# kapcsol.net
KiCad netlist of a schematic drawn in EAGLE
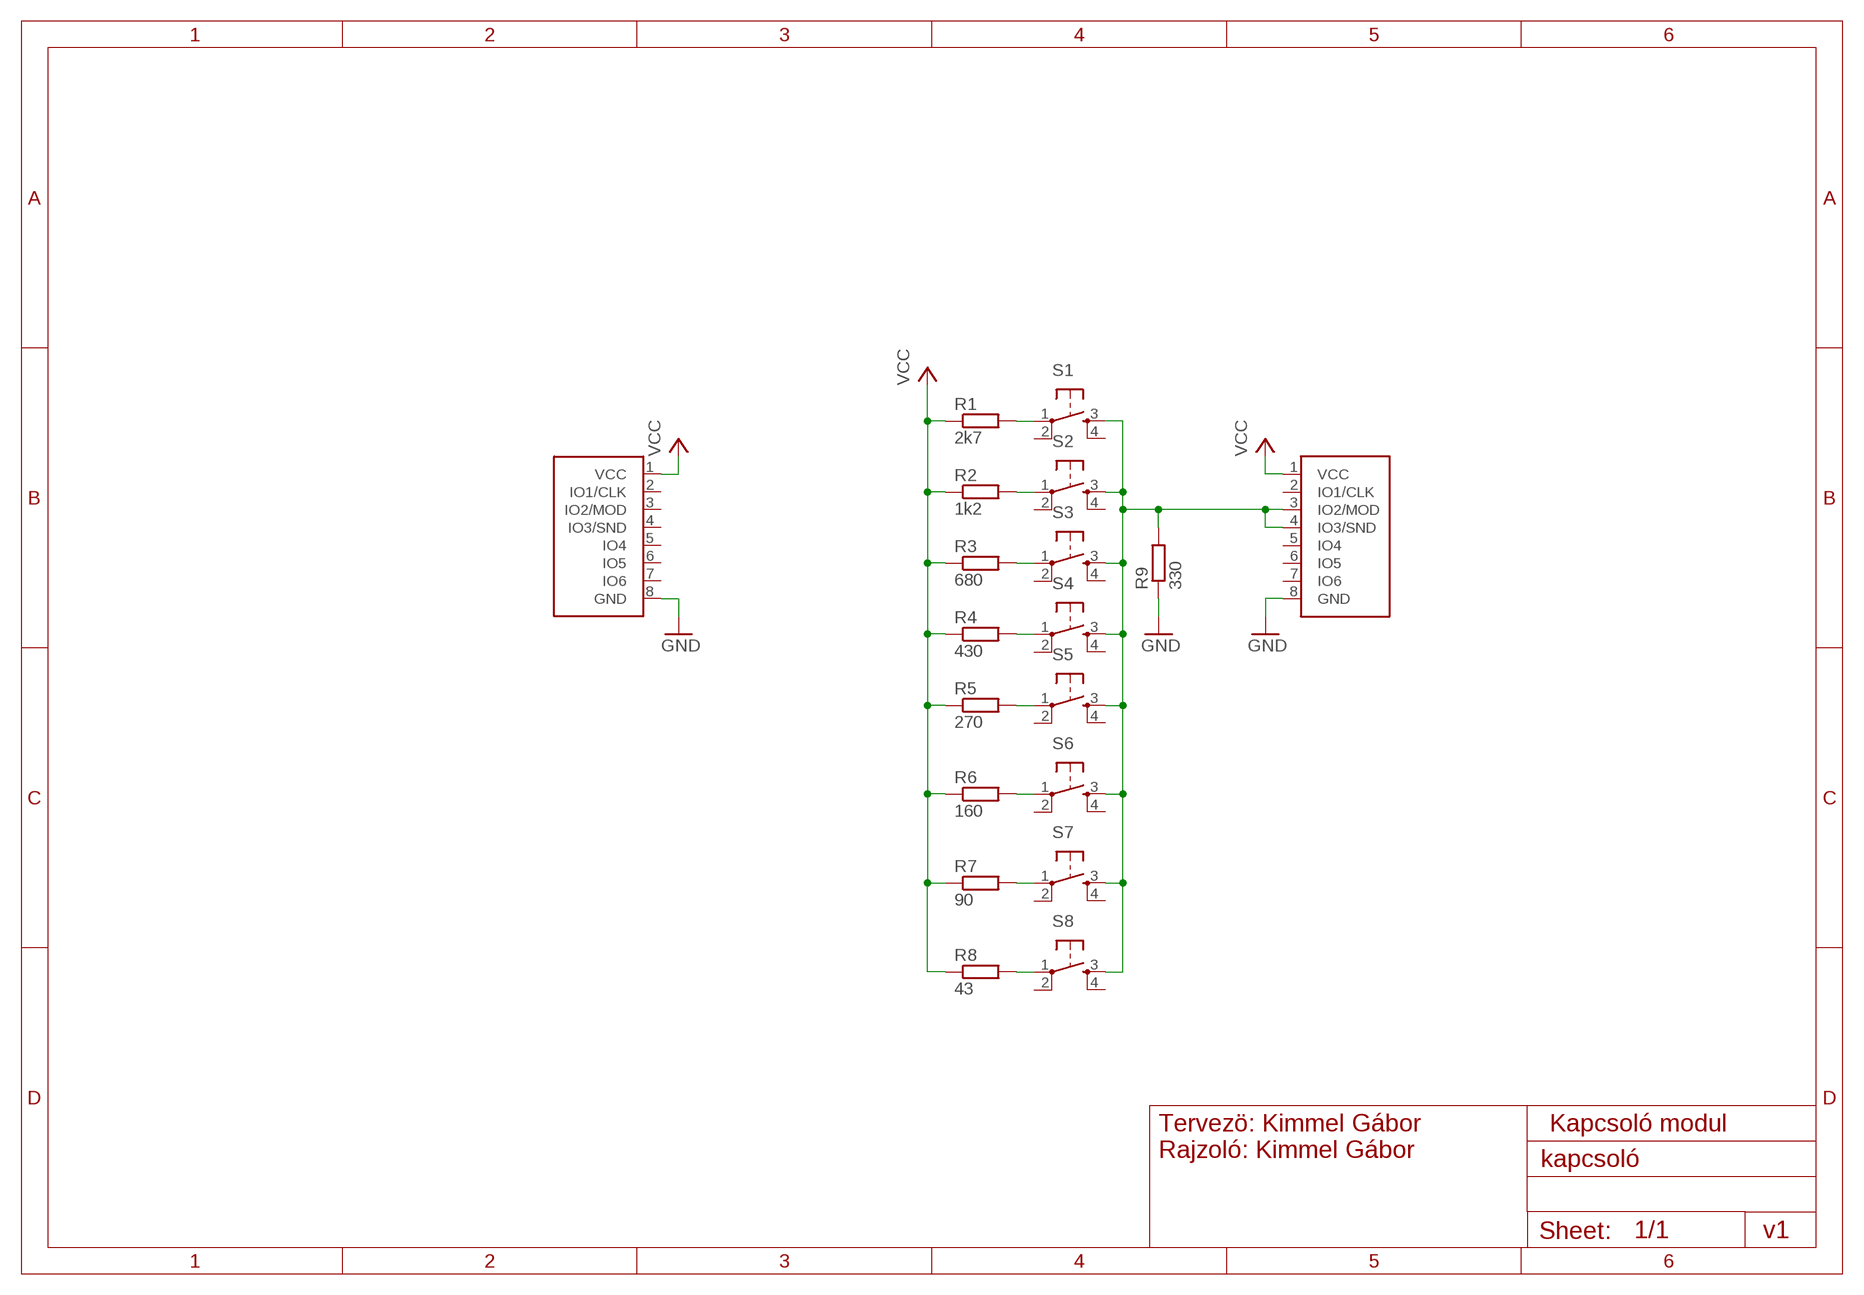
[diagram p0: schematic, sheet 1]

(export (version "E")
  (design (tool "Eeschema 10.0.6"))
  (components
    (comp (ref "R1")
      (value "2k7")
      (footprint "eagle-import:0309_12")
      (libsource (lib "eagle-import") (part "R-EU_0309/12"))
    )
    (comp (ref "R2")
      (value "1k2")
      (footprint "eagle-import:0309_12")
      (libsource (lib "eagle-import") (part "R-EU_0309/12"))
    )
    (comp (ref "R3")
      (value "680")
      (footprint "eagle-import:0309_12")
      (libsource (lib "eagle-import") (part "R-EU_0309/12"))
    )
    (comp (ref "R4")
      (value "430")
      (footprint "eagle-import:0309_12")
      (libsource (lib "eagle-import") (part "R-EU_0309/12"))
    )
    (comp (ref "R5")
      (value "270")
      (footprint "eagle-import:0309_12")
      (libsource (lib "eagle-import") (part "R-EU_0309/12"))
    )
    (comp (ref "R6")
      (value "160")
      (footprint "eagle-import:0309_12")
      (libsource (lib "eagle-import") (part "R-EU_0309/12"))
    )
    (comp (ref "R7")
      (value "90")
      (footprint "eagle-import:0309_12")
      (libsource (lib "eagle-import") (part "R-EU_0309/12"))
    )
    (comp (ref "R8")
      (value "43")
      (footprint "eagle-import:0309_12")
      (libsource (lib "eagle-import") (part "R-EU_0309/12"))
    )
    (comp (ref "R9")
      (value "330")
      (footprint "eagle-import:0309_12")
      (libsource (lib "eagle-import") (part "R-EU_0309/12"))
    )
    (comp (ref "S1")
      (value "TAC_SWITCHPTH")
      (footprint "eagle-import:TACTILE-PTH")
      (libsource (lib "eagle-import") (part "TAC_SWITCHPTH"))
    )
    (comp (ref "S2")
      (value "TAC_SWITCHPTH")
      (footprint "eagle-import:TACTILE-PTH")
      (libsource (lib "eagle-import") (part "TAC_SWITCHPTH"))
    )
    (comp (ref "S3")
      (value "TAC_SWITCHPTH")
      (footprint "eagle-import:TACTILE-PTH")
      (libsource (lib "eagle-import") (part "TAC_SWITCHPTH"))
    )
    (comp (ref "S4")
      (value "TAC_SWITCHPTH")
      (footprint "eagle-import:TACTILE-PTH")
      (libsource (lib "eagle-import") (part "TAC_SWITCHPTH"))
    )
    (comp (ref "S5")
      (value "TAC_SWITCHPTH")
      (footprint "eagle-import:TACTILE-PTH")
      (libsource (lib "eagle-import") (part "TAC_SWITCHPTH"))
    )
    (comp (ref "S6")
      (value "TAC_SWITCHPTH")
      (footprint "eagle-import:TACTILE-PTH")
      (libsource (lib "eagle-import") (part "TAC_SWITCHPTH"))
    )
    (comp (ref "S7")
      (value "TAC_SWITCHPTH")
      (footprint "eagle-import:TACTILE-PTH")
      (libsource (lib "eagle-import") (part "TAC_SWITCHPTH"))
    )
    (comp (ref "S8")
      (value "TAC_SWITCHPTH")
      (footprint "eagle-import:TACTILE-PTH")
      (libsource (lib "eagle-import") (part "TAC_SWITCHPTH"))
    )
    (comp (ref "U$1")
      (value "GANZ-CONNECTOR-OUT")
      (footprint "eagle-import:MA08-1W")
      (libsource (lib "eagle-import") (part "GANZ-CONNECTOR-OUT"))
    )
    (comp (ref "U$2")
      (value "GANZ-CONNECTOR")
      (footprint "eagle-import:FE08W")
      (libsource (lib "eagle-import") (part "GANZ-CONNECTOR"))
    )
  )
  (nets
    (net (code "1") (name "GND") (class "Default")
      (node (ref "R9") (pin "1") (pinfunction "1_1") (pintype "passive"))
      (node (ref "U$1") (pin "8") (pinfunction "GND_8") (pintype "bidirectional"))
      (node (ref "U$2") (pin "8") (pinfunction "GND_8") (pintype "bidirectional"))
    )
    (net (code "2") (name "Net-(R1-Pad2)") (class "Default")
      (node (ref "R1") (pin "2") (pinfunction "2_2") (pintype "passive"))
      (node (ref "S1") (pin "1") (pinfunction "1_1") (pintype "passive"))
    )
    (net (code "3") (name "Net-(R2-Pad2)") (class "Default")
      (node (ref "R2") (pin "2") (pinfunction "2_2") (pintype "passive"))
      (node (ref "S2") (pin "1") (pinfunction "1_1") (pintype "passive"))
    )
    (net (code "4") (name "Net-(R3-Pad2)") (class "Default")
      (node (ref "R3") (pin "2") (pinfunction "2_2") (pintype "passive"))
      (node (ref "S3") (pin "1") (pinfunction "1_1") (pintype "passive"))
    )
    (net (code "5") (name "Net-(R4-Pad2)") (class "Default")
      (node (ref "R4") (pin "2") (pinfunction "2_2") (pintype "passive"))
      (node (ref "S4") (pin "1") (pinfunction "1_1") (pintype "passive"))
    )
    (net (code "6") (name "Net-(R5-Pad2)") (class "Default")
      (node (ref "R5") (pin "2") (pinfunction "2_2") (pintype "passive"))
      (node (ref "S5") (pin "1") (pinfunction "1_1") (pintype "passive"))
    )
    (net (code "7") (name "Net-(R6-Pad2)") (class "Default")
      (node (ref "R6") (pin "2") (pinfunction "2_2") (pintype "passive"))
      (node (ref "S6") (pin "1") (pinfunction "1_1") (pintype "passive"))
    )
    (net (code "8") (name "Net-(R7-Pad2)") (class "Default")
      (node (ref "R7") (pin "2") (pinfunction "2_2") (pintype "passive"))
      (node (ref "S7") (pin "1") (pinfunction "1_1") (pintype "passive"))
    )
    (net (code "9") (name "Net-(R8-Pad2)") (class "Default")
      (node (ref "R8") (pin "2") (pinfunction "2_2") (pintype "passive"))
      (node (ref "S8") (pin "1") (pinfunction "1_1") (pintype "passive"))
    )
    (net (code "10") (name "Net-(U$1-IO2{slash}MOD)") (class "Default")
      (node (ref "R9") (pin "2") (pinfunction "2_2") (pintype "passive"))
      (node (ref "S1") (pin "3") (pinfunction "3_3") (pintype "passive"))
      (node (ref "S2") (pin "3") (pinfunction "3_3") (pintype "passive"))
      (node (ref "S3") (pin "3") (pinfunction "3_3") (pintype "passive"))
      (node (ref "S4") (pin "3") (pinfunction "3_3") (pintype "passive"))
      (node (ref "S5") (pin "3") (pinfunction "3_3") (pintype "passive"))
      (node (ref "S6") (pin "3") (pinfunction "3_3") (pintype "passive"))
      (node (ref "S7") (pin "3") (pinfunction "3_3") (pintype "passive"))
      (node (ref "S8") (pin "3") (pinfunction "3_3") (pintype "passive"))
      (node (ref "U$1") (pin "3") (pinfunction "IO2/MOD_3") (pintype "bidirectional"))
      (node (ref "U$1") (pin "4") (pinfunction "IO3/SND_4") (pintype "bidirectional"))
    )
    (net (code "11") (name "VCC") (class "Default")
      (node (ref "R1") (pin "1") (pinfunction "1_1") (pintype "passive"))
      (node (ref "R2") (pin "1") (pinfunction "1_1") (pintype "passive"))
      (node (ref "R3") (pin "1") (pinfunction "1_1") (pintype "passive"))
      (node (ref "R4") (pin "1") (pinfunction "1_1") (pintype "passive"))
      (node (ref "R5") (pin "1") (pinfunction "1_1") (pintype "passive"))
      (node (ref "R6") (pin "1") (pinfunction "1_1") (pintype "passive"))
      (node (ref "R7") (pin "1") (pinfunction "1_1") (pintype "passive"))
      (node (ref "R8") (pin "1") (pinfunction "1_1") (pintype "passive"))
      (node (ref "U$1") (pin "1") (pinfunction "VCC_1") (pintype "bidirectional"))
      (node (ref "U$2") (pin "1") (pinfunction "VCC_1") (pintype "bidirectional"))
    )
    (net (code "12") (name "unconnected-(S1-Pad2)") (class "Default")
      (node (ref "S1") (pin "2") (pinfunction "2_2") (pintype "passive"))
    )
    (net (code "13") (name "unconnected-(S1-Pad4)") (class "Default")
      (node (ref "S1") (pin "4") (pinfunction "4_4") (pintype "passive"))
    )
    (net (code "14") (name "unconnected-(S2-Pad2)") (class "Default")
      (node (ref "S2") (pin "2") (pinfunction "2_2") (pintype "passive"))
    )
    (net (code "15") (name "unconnected-(S2-Pad4)") (class "Default")
      (node (ref "S2") (pin "4") (pinfunction "4_4") (pintype "passive"))
    )
    (net (code "16") (name "unconnected-(S3-Pad2)") (class "Default")
      (node (ref "S3") (pin "2") (pinfunction "2_2") (pintype "passive"))
    )
    (net (code "17") (name "unconnected-(S3-Pad4)") (class "Default")
      (node (ref "S3") (pin "4") (pinfunction "4_4") (pintype "passive"))
    )
    (net (code "18") (name "unconnected-(S4-Pad2)") (class "Default")
      (node (ref "S4") (pin "2") (pinfunction "2_2") (pintype "passive"))
    )
    (net (code "19") (name "unconnected-(S4-Pad4)") (class "Default")
      (node (ref "S4") (pin "4") (pinfunction "4_4") (pintype "passive"))
    )
    (net (code "20") (name "unconnected-(S5-Pad2)") (class "Default")
      (node (ref "S5") (pin "2") (pinfunction "2_2") (pintype "passive"))
    )
    (net (code "21") (name "unconnected-(S5-Pad4)") (class "Default")
      (node (ref "S5") (pin "4") (pinfunction "4_4") (pintype "passive"))
    )
    (net (code "22") (name "unconnected-(S6-Pad2)") (class "Default")
      (node (ref "S6") (pin "2") (pinfunction "2_2") (pintype "passive"))
    )
    (net (code "23") (name "unconnected-(S6-Pad4)") (class "Default")
      (node (ref "S6") (pin "4") (pinfunction "4_4") (pintype "passive"))
    )
    (net (code "24") (name "unconnected-(S7-Pad2)") (class "Default")
      (node (ref "S7") (pin "2") (pinfunction "2_2") (pintype "passive"))
    )
    (net (code "25") (name "unconnected-(S7-Pad4)") (class "Default")
      (node (ref "S7") (pin "4") (pinfunction "4_4") (pintype "passive"))
    )
    (net (code "26") (name "unconnected-(S8-Pad2)") (class "Default")
      (node (ref "S8") (pin "2") (pinfunction "2_2") (pintype "passive"))
    )
    (net (code "27") (name "unconnected-(S8-Pad4)") (class "Default")
      (node (ref "S8") (pin "4") (pinfunction "4_4") (pintype "passive"))
    )
    (net (code "28") (name "unconnected-(U$1-IO1{slash}CLK-Pad2)") (class "Default")
      (node (ref "U$1") (pin "2") (pinfunction "IO1/CLK_2") (pintype "bidirectional"))
    )
    (net (code "29") (name "unconnected-(U$1-IO4-Pad5)") (class "Default")
      (node (ref "U$1") (pin "5") (pinfunction "IO4_5") (pintype "bidirectional"))
    )
    (net (code "30") (name "unconnected-(U$1-IO5-Pad6)") (class "Default")
      (node (ref "U$1") (pin "6") (pinfunction "IO5_6") (pintype "bidirectional"))
    )
    (net (code "31") (name "unconnected-(U$1-IO6-Pad7)") (class "Default")
      (node (ref "U$1") (pin "7") (pinfunction "IO6_7") (pintype "bidirectional"))
    )
    (net (code "32") (name "unconnected-(U$2-IO1{slash}CLK-Pad2)") (class "Default")
      (node (ref "U$2") (pin "2") (pinfunction "IO1/CLK_2") (pintype "bidirectional"))
    )
    (net (code "33") (name "unconnected-(U$2-IO2{slash}MOD-Pad3)") (class "Default")
      (node (ref "U$2") (pin "3") (pinfunction "IO2/MOD_3") (pintype "bidirectional"))
    )
    (net (code "34") (name "unconnected-(U$2-IO3{slash}SND-Pad4)") (class "Default")
      (node (ref "U$2") (pin "4") (pinfunction "IO3/SND_4") (pintype "bidirectional"))
    )
    (net (code "35") (name "unconnected-(U$2-IO4-Pad5)") (class "Default")
      (node (ref "U$2") (pin "5") (pinfunction "IO4_5") (pintype "bidirectional"))
    )
    (net (code "36") (name "unconnected-(U$2-IO5-Pad6)") (class "Default")
      (node (ref "U$2") (pin "6") (pinfunction "IO5_6") (pintype "bidirectional"))
    )
    (net (code "37") (name "unconnected-(U$2-IO6-Pad7)") (class "Default")
      (node (ref "U$2") (pin "7") (pinfunction "IO6_7") (pintype "bidirectional"))
    )
  )
)
